# uMultimeter__Sch_View.net
KiCad netlist of a schematic drawn in Altium Designer
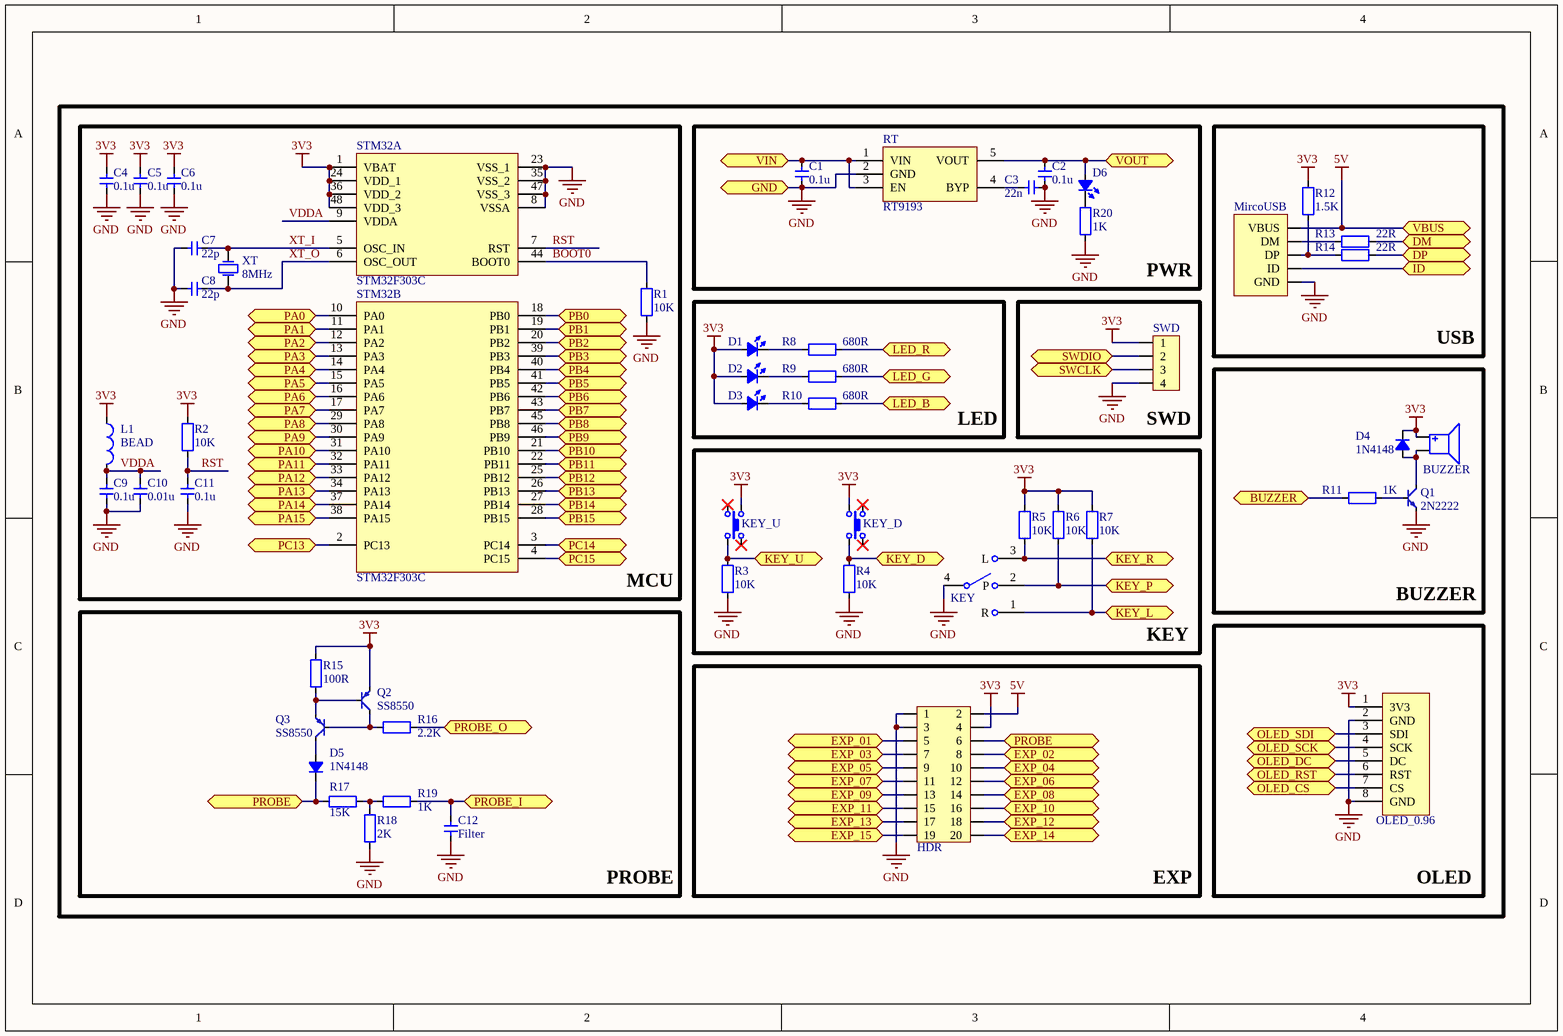
[diagram p0: uMultimeter__Sch_View.SchDoc]

(export (version "E")
  (design (tool "Eeschema 10.0.6"))
  (components
    (comp (ref "BUZZER")
      (value "Buzzer")
      (footprint "PCB_Module:Buzzer_5x5")
      (libsource (lib "SCH_Module") (part "Buzzer"))
    )
    (comp (ref "C1")
      (value "0.1u")
      (footprint "PCB_PassiveCap:CAP_0603")
      (description "Capacitor")
      (fields (field (name "Comment") "Cap_0603"))
      (libsource (lib "SCH_Passive") (part "Cap_0603"))
    )
    (comp (ref "C2")
      (value "0.1u")
      (footprint "PCB_PassiveCap:CAP_0603")
      (description "Capacitor")
      (fields (field (name "Comment") "Cap_0603"))
      (libsource (lib "SCH_Passive") (part "Cap_0603"))
    )
    (comp (ref "C3")
      (value "22n")
      (footprint "PCB_PassiveCap:CAP_0603")
      (description "Capacitor")
      (fields (field (name "Comment") "Cap_0603"))
      (libsource (lib "SCH_Passive") (part "Cap_0603"))
    )
    (comp (ref "C4")
      (value "0.1u")
      (footprint "PCB_PassiveCap:CAP_0603")
      (description "Capacitor")
      (fields (field (name "Comment") "Cap_0603"))
      (libsource (lib "SCH_Passive") (part "Cap_0603"))
    )
    (comp (ref "C5")
      (value "0.1u")
      (footprint "PCB_PassiveCap:CAP_0603")
      (description "Capacitor")
      (fields (field (name "Comment") "Cap_0603"))
      (libsource (lib "SCH_Passive") (part "Cap_0603"))
    )
    (comp (ref "C6")
      (value "0.1u")
      (footprint "PCB_PassiveCap:CAP_0603")
      (description "Capacitor")
      (fields (field (name "Comment") "Cap_0603"))
      (libsource (lib "SCH_Passive") (part "Cap_0603"))
    )
    (comp (ref "C7")
      (value "22p")
      (footprint "PCB_PassiveCap:CAP_0603")
      (description "Capacitor")
      (fields (field (name "Comment") "Cap_0603"))
      (libsource (lib "SCH_Passive") (part "Cap_0603"))
    )
    (comp (ref "C8")
      (value "22p")
      (footprint "PCB_PassiveCap:CAP_0603")
      (description "Capacitor")
      (fields (field (name "Comment") "Cap_0603"))
      (libsource (lib "SCH_Passive") (part "Cap_0603"))
    )
    (comp (ref "C9")
      (value "0.1u")
      (footprint "PCB_PassiveCap:CAP_0603")
      (description "Capacitor")
      (fields (field (name "Comment") "Cap_0603"))
      (libsource (lib "SCH_Passive") (part "Cap_0603"))
    )
    (comp (ref "C10")
      (value "0.01u")
      (footprint "PCB_PassiveCap:CAP_0603")
      (description "Capacitor")
      (fields (field (name "Comment") "Cap_0603"))
      (libsource (lib "SCH_Passive") (part "Cap_0603"))
    )
    (comp (ref "C11")
      (value "0.1u")
      (footprint "PCB_PassiveCap:CAP_0603")
      (description "Capacitor")
      (fields (field (name "Comment") "Cap_0603"))
      (libsource (lib "SCH_Passive") (part "Cap_0603"))
    )
    (comp (ref "C12")
      (value "Filter")
      (footprint "PCB_PassiveCap:CAP_0603")
      (description "Capacitor")
      (fields (field (name "Comment") "Cap_0603"))
      (libsource (lib "SCH_Passive") (part "Cap_0603"))
    )
    (comp (ref "D1")
      (value "LED_0805")
      (footprint "PCB_ActiveLED:LED_0805_RED")
      (description "LED")
      (libsource (lib "SCH_Active") (part "LED_0805"))
    )
    (comp (ref "D2")
      (value "LED_0805")
      (footprint "PCB_ActiveLED:LED_0805_GREEN")
      (description "LED")
      (libsource (lib "SCH_Active") (part "LED_0805"))
    )
    (comp (ref "D3")
      (value "LED_0805")
      (footprint "PCB_ActiveLED:LED_0805_BLUE")
      (description "LED")
      (libsource (lib "SCH_Active") (part "LED_0805"))
    )
    (comp (ref "D4")
      (value "1N4148")
      (footprint "PCB_ActiveDIO:SOD-323")
      (description "Diode")
      (fields (field (name "Comment") "Diode_SOD323"))
      (libsource (lib "SCH_Active") (part "Diode_SOD323"))
    )
    (comp (ref "D5")
      (value "1N4148")
      (footprint "PCB_ActiveDIO:SOD-323")
      (description "Diode")
      (fields (field (name "Comment") "Diode_SOD323"))
      (libsource (lib "SCH_Active") (part "Diode_SOD323"))
    )
    (comp (ref "D6")
      (value "LED_0805")
      (footprint "PCB_ActiveLED:LED_0805_ORANGE")
      (description "LED")
      (libsource (lib "SCH_Active") (part "LED_0805"))
    )
    (comp (ref "HDR")
      (value "HDR2x10_2.54")
      (footprint "PCB_ConnectorHDR:HDR2X10_2.54_180HF")
      (description "Header")
      (libsource (lib "SCH_ConnectorHDR") (part "HDR2x10_2.54"))
    )
    (comp (ref "KEY")
      (value "ButtonPushLever_11*12_90")
      (footprint "PCB_Switch:ButtonPushLever_11*12_90")
      (description "Button")
      (libsource (lib "SCH_Switch") (part "ButtonPushLever_11*12_90"))
    )
    (comp (ref "KEY_D")
      (value "ButtonTACT")
      (footprint "PCB_Switch:ButtonTACT_3.5*3.55_90")
      (description "Button")
      (libsource (lib "SCH_Switch") (part "ButtonTACT"))
    )
    (comp (ref "KEY_U")
      (value "ButtonTACT")
      (footprint "PCB_Switch:ButtonTACT_3.5*3.55_90")
      (description "Button")
      (libsource (lib "SCH_Switch") (part "ButtonTACT"))
    )
    (comp (ref "L1")
      (value "BEAD")
      (footprint "PCB_PassiveInd:IND_0603")
      (description "Inductor")
      (fields (field (name "Comment") "Ind_0603"))
      (libsource (lib "SCH_Passive") (part "Ind_0603"))
    )
    (comp (ref "MircoUSB")
      (value "USB_Micro")
      (footprint "PCB_USB:USB_Micro-AB")
      (description "USB")
      (libsource (lib "SCH_USB") (part "USB_Micro"))
    )
    (comp (ref "OLED_0.96")
      (value "OLED_0.96")
      (footprint "PCB_Module:OLED_0.96_96x64_v2")
      (description "Module")
      (libsource (lib "SCH_Module") (part "OLED_0.96_96*64_v2"))
    )
    (comp (ref "Q1")
      (value "2N2222")
      (footprint "PCB_IntegratedCircuit:SOT23-3")
      (description "Transistor")
      (fields (field (name "Comment") "BJT_NPN"))
      (libsource (lib "SCH_Active") (part "BJT_NPN"))
    )
    (comp (ref "Q2")
      (value "SS8550")
      (footprint "PCB_IntegratedCircuit:SOT23-3")
      (description "Transistor")
      (fields (field (name "Comment") "BJT_PNP"))
      (libsource (lib "SCH_Active") (part "BJT_PNP"))
    )
    (comp (ref "Q3")
      (value "SS8550")
      (footprint "PCB_IntegratedCircuit:SOT23-3")
      (description "Transistor")
      (fields (field (name "Comment") "BJT_PNP"))
      (libsource (lib "SCH_Active") (part "BJT_PNP"))
    )
    (comp (ref "R1")
      (value "10K")
      (footprint "PCB_PassiveRes:RES_0603")
      (description "Resistor")
      (fields (field (name "Comment") "Res_0603"))
      (libsource (lib "") (part "Res_0603_1"))
    )
    (comp (ref "R2")
      (value "10K")
      (footprint "PCB_PassiveRes:RES_0603")
      (description "Resistor")
      (fields (field (name "Comment") "Res_0603"))
      (libsource (lib "") (part "Res_0603_1"))
    )
    (comp (ref "R3")
      (value "10K")
      (footprint "PCB_PassiveRes:RES_0603")
      (description "Resistor")
      (fields (field (name "Comment") "Res_0603"))
      (libsource (lib "") (part "Res_0603_1"))
    )
    (comp (ref "R4")
      (value "10K")
      (footprint "PCB_PassiveRes:RES_0603")
      (description "Resistor")
      (fields (field (name "Comment") "Res_0603"))
      (libsource (lib "") (part "Res_0603_1"))
    )
    (comp (ref "R5")
      (value "10K")
      (footprint "PCB_PassiveRes:RES_0603")
      (description "Resistor")
      (fields (field (name "Comment") "Res_0603"))
      (libsource (lib "") (part "Res_0603_1"))
    )
    (comp (ref "R6")
      (value "10K")
      (footprint "PCB_PassiveRes:RES_0603")
      (description "Resistor")
      (fields (field (name "Comment") "Res_0603"))
      (libsource (lib "") (part "Res_0603_1"))
    )
    (comp (ref "R7")
      (value "10K")
      (footprint "PCB_PassiveRes:RES_0603")
      (description "Resistor")
      (fields (field (name "Comment") "Res_0603"))
      (libsource (lib "") (part "Res_0603_1"))
    )
    (comp (ref "R8")
      (value "680R")
      (footprint "PCB_PassiveRes:RES_0603")
      (description "Resistor")
      (fields (field (name "Comment") "Res_0603"))
      (libsource (lib "SCH_Passive") (part "Res_0603"))
    )
    (comp (ref "R9")
      (value "680R")
      (footprint "PCB_PassiveRes:RES_0603")
      (description "Resistor")
      (fields (field (name "Comment") "Res_0603"))
      (libsource (lib "SCH_Passive") (part "Res_0603"))
    )
    (comp (ref "R10")
      (value "680R")
      (footprint "PCB_PassiveRes:RES_0603")
      (description "Resistor")
      (fields (field (name "Comment") "Res_0603"))
      (libsource (lib "") (part "Res_0603_2"))
    )
    (comp (ref "R11")
      (value "1K")
      (footprint "PCB_PassiveRes:RES_0603")
      (description "Resistor")
      (fields (field (name "Comment") "Res_0603"))
      (libsource (lib "SCH_Passive") (part "Res_0603"))
    )
    (comp (ref "R12")
      (value "1.5K")
      (footprint "PCB_PassiveRes:RES_0603")
      (description "Resistor")
      (fields (field (name "Comment") "Res_0603"))
      (libsource (lib "") (part "Res_0603_3"))
    )
    (comp (ref "R13")
      (value "22R")
      (footprint "PCB_PassiveRes:RES_0603")
      (description "Resistor")
      (fields (field (name "Comment") "Res_0603"))
      (libsource (lib "") (part "Res_0603_2"))
    )
    (comp (ref "R14")
      (value "22R")
      (footprint "PCB_PassiveRes:RES_0603")
      (description "Resistor")
      (fields (field (name "Comment") "Res_0603"))
      (libsource (lib "") (part "Res_0603_2"))
    )
    (comp (ref "R15")
      (value "100R")
      (footprint "PCB_PassiveRes:RES_0603")
      (description "Resistor")
      (fields (field (name "Comment") "Res_0603"))
      (libsource (lib "") (part "Res_0603_1"))
    )
    (comp (ref "R16")
      (value "2.2K")
      (footprint "PCB_PassiveRes:RES_0603")
      (description "Resistor")
      (fields (field (name "Comment") "Res_0603"))
      (libsource (lib "SCH_Passive") (part "Res_0603"))
    )
    (comp (ref "R17")
      (value "15K")
      (footprint "PCB_PassiveRes:RES_0603")
      (description "Resistor")
      (fields (field (name "Comment") "Res_0603"))
      (libsource (lib "SCH_Passive") (part "Res_0603"))
    )
    (comp (ref "R18")
      (value "2K")
      (footprint "PCB_PassiveRes:RES_0603")
      (description "Resistor")
      (fields (field (name "Comment") "Res_0603"))
      (libsource (lib "") (part "Res_0603_3"))
    )
    (comp (ref "R19")
      (value "1K")
      (footprint "PCB_PassiveRes:RES_0603")
      (description "Resistor")
      (fields (field (name "Comment") "Res_0603"))
      (libsource (lib "") (part "Res_0603_2"))
    )
    (comp (ref "R20")
      (value "1K")
      (footprint "PCB_PassiveRes:RES_0603")
      (description "Resistor")
      (fields (field (name "Comment") "Res_0603"))
      (libsource (lib "") (part "Res_0603_3"))
    )
    (comp (ref "RT")
      (value "RT9193")
      (footprint "PCB_IntegratedCircuit:SOT23-5")
      (description "Power")
      (libsource (lib "SCH_IntegratedCircuit") (part "SP6205"))
    )
    (comp (ref "STM32")
      (value "STM32F303C")
      (footprint "PCB_IntegratedCircuit:LQFP_P0.5_48")
      (description "MCU")
      (libsource (lib "SCH_IntegratedCircuit") (part "STM32F303C"))
    )
    (comp (ref "SWD")
      (value "HDR1x4_1.27")
      (footprint "PCB_ConnectorHDR:HDR1X4_1.27_180")
      (description "Header")
      (libsource (lib "SCH_ConnectorHDR") (part "HDR1x4_1.27"))
    )
    (comp (ref "XT")
      (value "8MHz")
      (footprint "PCB_Oscillator:XT_5032_2")
      (description "Crystal Oscillator")
      (fields (field (name "Comment") "XTAL_5032_2P"))
      (libsource (lib "SCH_Oscillator") (part "XTAL_5032_2P"))
    )
  )
  (nets
    (net (code "1") (name "/BOOT0") (class "Default")
      (node (ref "R1") (pin "2") (pinfunction "2_2") (pintype "passive"))
      (node (ref "STM32") (pin "44") (pinfunction "BOOT0_44") (pintype "passive"))
    )
    (net (code "2") (name "/BUZZER") (class "Default")
      (node (ref "R11") (pin "2") (pinfunction "2_2") (pintype "passive"))
    )
    (net (code "3") (name "/DM") (class "Default")
      (node (ref "R13") (pin "2") (pinfunction "2_2") (pintype "passive"))
    )
    (net (code "4") (name "/DP") (class "Default")
      (node (ref "R14") (pin "2") (pinfunction "2_2") (pintype "passive"))
    )
    (net (code "5") (name "/EXP_01") (class "Default")
      (node (ref "HDR") (pin "5") (pinfunction "5_5") (pintype "passive"))
    )
    (net (code "6") (name "/EXP_02") (class "Default")
      (node (ref "HDR") (pin "8") (pinfunction "8_8") (pintype "passive"))
    )
    (net (code "7") (name "/EXP_03") (class "Default")
      (node (ref "HDR") (pin "7") (pinfunction "7_7") (pintype "passive"))
    )
    (net (code "8") (name "/EXP_04") (class "Default")
      (node (ref "HDR") (pin "10") (pinfunction "10_10") (pintype "passive"))
    )
    (net (code "9") (name "/EXP_05") (class "Default")
      (node (ref "HDR") (pin "9") (pinfunction "9_9") (pintype "passive"))
    )
    (net (code "10") (name "/EXP_06") (class "Default")
      (node (ref "HDR") (pin "12") (pinfunction "12_12") (pintype "passive"))
    )
    (net (code "11") (name "/EXP_07") (class "Default")
      (node (ref "HDR") (pin "11") (pinfunction "11_11") (pintype "passive"))
    )
    (net (code "12") (name "/EXP_08") (class "Default")
      (node (ref "HDR") (pin "14") (pinfunction "14_14") (pintype "passive"))
    )
    (net (code "13") (name "/EXP_09") (class "Default")
      (node (ref "HDR") (pin "13") (pinfunction "13_13") (pintype "passive"))
    )
    (net (code "14") (name "/EXP_10") (class "Default")
      (node (ref "HDR") (pin "16") (pinfunction "16_16") (pintype "passive"))
    )
    (net (code "15") (name "/EXP_11") (class "Default")
      (node (ref "HDR") (pin "15") (pinfunction "15_15") (pintype "passive"))
    )
    (net (code "16") (name "/EXP_12") (class "Default")
      (node (ref "HDR") (pin "18") (pinfunction "18_18") (pintype "passive"))
    )
    (net (code "17") (name "/EXP_13") (class "Default")
      (node (ref "HDR") (pin "17") (pinfunction "17_17") (pintype "passive"))
    )
    (net (code "18") (name "/EXP_14") (class "Default")
      (node (ref "HDR") (pin "20") (pinfunction "20_20") (pintype "passive"))
    )
    (net (code "19") (name "/EXP_15") (class "Default")
      (node (ref "HDR") (pin "19") (pinfunction "19_19") (pintype "passive"))
    )
    (net (code "20") (name "/ID") (class "Default")
      (node (ref "MircoUSB") (pin "4") (pinfunction "ID_4") (pintype "passive"))
    )
    (net (code "21") (name "/KEY_D") (class "Default")
      (node (ref "KEY_D") (pin "4") (pinfunction "4_4") (pintype "passive"))
      (node (ref "R4") (pin "2") (pinfunction "2_2") (pintype "passive"))
    )
    (net (code "22") (name "/KEY_L") (class "Default")
      (node (ref "KEY") (pin "1") (pinfunction "R_1") (pintype "passive"))
      (node (ref "R7") (pin "1") (pinfunction "1_1") (pintype "passive"))
    )
    (net (code "23") (name "/KEY_P") (class "Default")
      (node (ref "KEY") (pin "2") (pinfunction "P_2") (pintype "passive"))
      (node (ref "R6") (pin "1") (pinfunction "1_1") (pintype "passive"))
    )
    (net (code "24") (name "/KEY_R") (class "Default")
      (node (ref "KEY") (pin "3") (pinfunction "L_3") (pintype "passive"))
      (node (ref "R5") (pin "1") (pinfunction "1_1") (pintype "passive"))
    )
    (net (code "25") (name "/KEY_U") (class "Default")
      (node (ref "KEY_U") (pin "4") (pinfunction "4_4") (pintype "passive"))
      (node (ref "R3") (pin "2") (pinfunction "2_2") (pintype "passive"))
    )
    (net (code "26") (name "/LED_B") (class "Default")
      (node (ref "R10") (pin "2") (pinfunction "2_2") (pintype "passive"))
    )
    (net (code "27") (name "/LED_G") (class "Default")
      (node (ref "R9") (pin "1") (pinfunction "1_1") (pintype "passive"))
    )
    (net (code "28") (name "/LED_R") (class "Default")
      (node (ref "R8") (pin "1") (pinfunction "1_1") (pintype "passive"))
    )
    (net (code "29") (name "/OLED_CS") (class "Default")
      (node (ref "OLED_0.96") (pin "7") (pinfunction "CS_7") (pintype "passive"))
    )
    (net (code "30") (name "/OLED_DC") (class "Default")
      (node (ref "OLED_0.96") (pin "5") (pinfunction "DC_5") (pintype "passive"))
    )
    (net (code "31") (name "/OLED_RST") (class "Default")
      (node (ref "OLED_0.96") (pin "6") (pinfunction "RST_6") (pintype "passive"))
    )
    (net (code "32") (name "/OLED_SCK") (class "Default")
      (node (ref "OLED_0.96") (pin "4") (pinfunction "SCK_4") (pintype "passive"))
    )
    (net (code "33") (name "/OLED_SDI") (class "Default")
      (node (ref "OLED_0.96") (pin "3") (pinfunction "SDI_3") (pintype "passive"))
    )
    (net (code "34") (name "/PA0") (class "Default")
      (node (ref "STM32") (pin "10") (pinfunction "PA0_10") (pintype "passive"))
    )
    (net (code "35") (name "/PA1") (class "Default")
      (node (ref "STM32") (pin "11") (pinfunction "PA1_11") (pintype "passive"))
    )
    (net (code "36") (name "/PA2") (class "Default")
      (node (ref "STM32") (pin "12") (pinfunction "PA2_12") (pintype "passive"))
    )
    (net (code "37") (name "/PA3") (class "Default")
      (node (ref "STM32") (pin "13") (pinfunction "PA3_13") (pintype "passive"))
    )
    (net (code "38") (name "/PA4") (class "Default")
      (node (ref "STM32") (pin "14") (pinfunction "PA4_14") (pintype "passive"))
    )
    (net (code "39") (name "/PA5") (class "Default")
      (node (ref "STM32") (pin "15") (pinfunction "PA5_15") (pintype "passive"))
    )
    (net (code "40") (name "/PA6") (class "Default")
      (node (ref "STM32") (pin "16") (pinfunction "PA6_16") (pintype "passive"))
    )
    (net (code "41") (name "/PA7") (class "Default")
      (node (ref "STM32") (pin "17") (pinfunction "PA7_17") (pintype "passive"))
    )
    (net (code "42") (name "/PA8") (class "Default")
      (node (ref "STM32") (pin "29") (pinfunction "PA8_29") (pintype "passive"))
    )
    (net (code "43") (name "/PA9") (class "Default")
      (node (ref "STM32") (pin "30") (pinfunction "PA9_30") (pintype "passive"))
    )
    (net (code "44") (name "/PA10") (class "Default")
      (node (ref "STM32") (pin "31") (pinfunction "PA10_31") (pintype "passive"))
    )
    (net (code "45") (name "/PA11") (class "Default")
      (node (ref "STM32") (pin "32") (pinfunction "PA11_32") (pintype "passive"))
    )
    (net (code "46") (name "/PA12") (class "Default")
      (node (ref "STM32") (pin "33") (pinfunction "PA12_33") (pintype "passive"))
    )
    (net (code "47") (name "/PA13") (class "Default")
      (node (ref "STM32") (pin "34") (pinfunction "PA13_34") (pintype "passive"))
    )
    (net (code "48") (name "/PA14") (class "Default")
      (node (ref "STM32") (pin "37") (pinfunction "PA14_37") (pintype "passive"))
    )
    (net (code "49") (name "/PA15") (class "Default")
      (node (ref "STM32") (pin "38") (pinfunction "PA15_38") (pintype "passive"))
    )
    (net (code "50") (name "/PB0") (class "Default")
      (node (ref "STM32") (pin "18") (pinfunction "PB0_18") (pintype "passive"))
    )
    (net (code "51") (name "/PB1") (class "Default")
      (node (ref "STM32") (pin "19") (pinfunction "PB1_19") (pintype "passive"))
    )
    (net (code "52") (name "/PB2") (class "Default")
      (node (ref "STM32") (pin "20") (pinfunction "PB2_20") (pintype "passive"))
    )
    (net (code "53") (name "/PB3") (class "Default")
      (node (ref "STM32") (pin "39") (pinfunction "PB3_39") (pintype "passive"))
    )
    (net (code "54") (name "/PB4") (class "Default")
      (node (ref "STM32") (pin "40") (pinfunction "PB4_40") (pintype "passive"))
    )
    (net (code "55") (name "/PB5") (class "Default")
      (node (ref "STM32") (pin "41") (pinfunction "PB5_41") (pintype "passive"))
    )
    (net (code "56") (name "/PB6") (class "Default")
      (node (ref "STM32") (pin "42") (pinfunction "PB6_42") (pintype "passive"))
    )
    (net (code "57") (name "/PB7") (class "Default")
      (node (ref "STM32") (pin "43") (pinfunction "PB7_43") (pintype "passive"))
    )
    (net (code "58") (name "/PB8") (class "Default")
      (node (ref "STM32") (pin "45") (pinfunction "PB8_45") (pintype "passive"))
    )
    (net (code "59") (name "/PB9") (class "Default")
      (node (ref "STM32") (pin "46") (pinfunction "PB9_46") (pintype "passive"))
    )
    (net (code "60") (name "/PB10") (class "Default")
      (node (ref "STM32") (pin "21") (pinfunction "PB10_21") (pintype "passive"))
    )
    (net (code "61") (name "/PB11") (class "Default")
      (node (ref "STM32") (pin "22") (pinfunction "PB11_22") (pintype "passive"))
    )
    (net (code "62") (name "/PB12") (class "Default")
      (node (ref "STM32") (pin "25") (pinfunction "PB12_25") (pintype "passive"))
    )
    (net (code "63") (name "/PB13") (class "Default")
      (node (ref "STM32") (pin "26") (pinfunction "PB13_26") (pintype "passive"))
    )
    (net (code "64") (name "/PB14") (class "Default")
      (node (ref "STM32") (pin "27") (pinfunction "PB14_27") (pintype "passive"))
    )
    (net (code "65") (name "/PB15") (class "Default")
      (node (ref "STM32") (pin "28") (pinfunction "PB15_28") (pintype "passive"))
    )
    (net (code "66") (name "/PC13") (class "Default")
      (node (ref "STM32") (pin "2") (pinfunction "PC13_2") (pintype "passive"))
    )
    (net (code "67") (name "/PC14") (class "Default")
      (node (ref "STM32") (pin "3") (pinfunction "PC14_3") (pintype "passive"))
    )
    (net (code "68") (name "/PC15") (class "Default")
      (node (ref "STM32") (pin "4") (pinfunction "PC15_4") (pintype "passive"))
    )
    (net (code "69") (name "/PROBE") (class "Default")
      (node (ref "D5") (pin "2") (pinfunction "K_2") (pintype "passive"))
      (node (ref "HDR") (pin "6") (pinfunction "6_6") (pintype "passive"))
      (node (ref "R17") (pin "2") (pinfunction "2_2") (pintype "passive"))
    )
    (net (code "70") (name "/PROBE_I") (class "Default")
      (node (ref "C12") (pin "2") (pinfunction "2_2") (pintype "passive"))
      (node (ref "R19") (pin "2") (pinfunction "2_2") (pintype "passive"))
    )
    (net (code "71") (name "/PROBE_O") (class "Default")
      (node (ref "R16") (pin "1") (pinfunction "1_1") (pintype "passive"))
    )
    (net (code "72") (name "/RST") (class "Default")
      (node (ref "C11") (pin "2") (pinfunction "2_2") (pintype "passive"))
      (node (ref "R2") (pin "1") (pinfunction "1_1") (pintype "passive"))
      (node (ref "STM32") (pin "7") (pinfunction "RST_7") (pintype "passive"))
    )
    (net (code "73") (name "/SWCLK") (class "Default")
      (node (ref "SWD") (pin "3") (pinfunction "3_3") (pintype "passive"))
    )
    (net (code "74") (name "/SWDIO") (class "Default")
      (node (ref "SWD") (pin "2") (pinfunction "2_2") (pintype "passive"))
    )
    (net (code "75") (name "/VDDA") (class "Default")
      (node (ref "C10") (pin "2") (pinfunction "2_2") (pintype "passive"))
      (node (ref "C9") (pin "2") (pinfunction "2_2") (pintype "passive"))
      (node (ref "L1") (pin "2") (pinfunction "2_2") (pintype "passive"))
      (node (ref "STM32") (pin "9") (pinfunction "VDDA_9") (pintype "passive"))
    )
    (net (code "76") (name "/VIN") (class "Default")
      (node (ref "C1") (pin "2") (pinfunction "2_2") (pintype "passive"))
      (node (ref "RT") (pin "1") (pinfunction "VIN_1") (pintype "passive"))
      (node (ref "RT") (pin "3") (pinfunction "EN_3") (pintype "power_in"))
    )
    (net (code "77") (name "/VOUT") (class "Default")
      (node (ref "C2") (pin "2") (pinfunction "2_2") (pintype "passive"))
      (node (ref "D6") (pin "1") (pinfunction "A_1") (pintype "passive"))
      (node (ref "RT") (pin "5") (pinfunction "VOUT_5") (pintype "passive"))
    )
    (net (code "78") (name "/XT_I") (class "Default")
      (node (ref "C7") (pin "1") (pinfunction "1_1") (pintype "passive"))
      (node (ref "STM32") (pin "5") (pinfunction "OSC_IN_5") (pintype "passive"))
      (node (ref "XT") (pin "2") (pinfunction "OSC2_2") (pintype "passive"))
    )
    (net (code "79") (name "/XT_O") (class "Default")
      (node (ref "C8") (pin "1") (pinfunction "1_1") (pintype "passive"))
      (node (ref "STM32") (pin "6") (pinfunction "OSC_OUT_6") (pintype "passive"))
      (node (ref "XT") (pin "1") (pinfunction "OSC1_1") (pintype "passive"))
    )
    (net (code "80") (name "3V3") (class "Default")
      (node (ref "BUZZER") (pin "P") (pinfunction "Positive_P") (pintype "passive"))
      (node (ref "C4") (pin "2") (pinfunction "2_2") (pintype "passive"))
      (node (ref "C5") (pin "2") (pinfunction "2_2") (pintype "passive"))
      (node (ref "C6") (pin "2") (pinfunction "2_2") (pintype "passive"))
      (node (ref "D1") (pin "1") (pinfunction "A_1") (pintype "passive"))
      (node (ref "D2") (pin "1") (pinfunction "A_1") (pintype "passive"))
      (node (ref "D3") (pin "1") (pinfunction "A_1") (pintype "passive"))
      (node (ref "D4") (pin "2") (pinfunction "K_2") (pintype "passive"))
      (node (ref "HDR") (pin "4") (pinfunction "4_4") (pintype "passive"))
      (node (ref "KEY_D") (pin "3") (pinfunction "3_3") (pintype "passive"))
      (node (ref "KEY_U") (pin "1") (pinfunction "1_1") (pintype "passive"))
      (node (ref "L1") (pin "1") (pinfunction "1_1") (pintype "passive"))
      (node (ref "OLED_0.96") (pin "1") (pinfunction "3V3_1") (pintype "passive"))
      (node (ref "Q2") (pin "2") (pinfunction "E_2") (pintype "passive"))
      (node (ref "R12") (pin "1") (pinfunction "1_1") (pintype "passive"))
      (node (ref "R15") (pin "2") (pinfunction "2_2") (pintype "passive"))
      (node (ref "R2") (pin "2") (pinfunction "2_2") (pintype "passive"))
      (node (ref "R5") (pin "2") (pinfunction "2_2") (pintype "passive"))
      (node (ref "R6") (pin "2") (pinfunction "2_2") (pintype "passive"))
      (node (ref "R7") (pin "2") (pinfunction "2_2") (pintype "passive"))
      (node (ref "STM32") (pin "1") (pinfunction "VBAT_1") (pintype "passive"))
      (node (ref "STM32") (pin "24") (pinfunction "VDD_1_24") (pintype "passive"))
      (node (ref "STM32") (pin "36") (pinfunction "VDD_2_36") (pintype "passive"))
      (node (ref "STM32") (pin "48") (pinfunction "VDD_3_48") (pintype "passive"))
      (node (ref "SWD") (pin "1") (pinfunction "1_1") (pintype "passive"))
    )
    (net (code "81") (name "5V") (class "Default")
      (node (ref "HDR") (pin "2") (pinfunction "2_2") (pintype "passive"))
      (node (ref "MircoUSB") (pin "1") (pinfunction "VBUS_1") (pintype "passive"))
    )
    (net (code "82") (name "GND") (class "Default")
      (node (ref "C1") (pin "1") (pinfunction "1_1") (pintype "passive"))
      (node (ref "C10") (pin "1") (pinfunction "1_1") (pintype "passive"))
      (node (ref "C11") (pin "1") (pinfunction "1_1") (pintype "passive"))
      (node (ref "C12") (pin "1") (pinfunction "1_1") (pintype "passive"))
      (node (ref "C2") (pin "1") (pinfunction "1_1") (pintype "passive"))
      (node (ref "C3") (pin "1") (pinfunction "1_1") (pintype "passive"))
      (node (ref "C4") (pin "1") (pinfunction "1_1") (pintype "passive"))
      (node (ref "C5") (pin "1") (pinfunction "1_1") (pintype "passive"))
      (node (ref "C6") (pin "1") (pinfunction "1_1") (pintype "passive"))
      (node (ref "C7") (pin "2") (pinfunction "2_2") (pintype "passive"))
      (node (ref "C8") (pin "2") (pinfunction "2_2") (pintype "passive"))
      (node (ref "C9") (pin "1") (pinfunction "1_1") (pintype "passive"))
      (node (ref "HDR") (pin "1") (pinfunction "1_1") (pintype "passive"))
      (node (ref "HDR") (pin "3") (pinfunction "3_3") (pintype "passive"))
      (node (ref "KEY") (pin "4") (pinfunction "4_4") (pintype "passive"))
      (node (ref "MircoUSB") (pin "5") (pinfunction "GND_5") (pintype "passive"))
      (node (ref "OLED_0.96") (pin "2") (pinfunction "GND_2") (pintype "passive"))
      (node (ref "OLED_0.96") (pin "8") (pinfunction "GND_8") (pintype "passive"))
      (node (ref "Q1") (pin "2") (pinfunction "E_2") (pintype "passive"))
      (node (ref "R1") (pin "1") (pinfunction "1_1") (pintype "passive"))
      (node (ref "R18") (pin "2") (pinfunction "2_2") (pintype "passive"))
      (node (ref "R20") (pin "2") (pinfunction "2_2") (pintype "passive"))
      (node (ref "R3") (pin "1") (pinfunction "1_1") (pintype "passive"))
      (node (ref "R4") (pin "1") (pinfunction "1_1") (pintype "passive"))
      (node (ref "RT") (pin "2") (pinfunction "GND_2") (pintype "passive"))
      (node (ref "STM32") (pin "23") (pinfunction "VSS_1_23") (pintype "passive"))
      (node (ref "STM32") (pin "35") (pinfunction "VSS_2_35") (pintype "passive"))
      (node (ref "STM32") (pin "47") (pinfunction "VSS_3_47") (pintype "passive"))
      (node (ref "STM32") (pin "8") (pinfunction "VSSA_8") (pintype "passive"))
      (node (ref "SWD") (pin "4") (pinfunction "4_4") (pintype "passive"))
    )
    (net (code "83") (name "Net-(BUZZER-Negative)") (class "Default")
      (node (ref "BUZZER") (pin "N") (pinfunction "Negative_N") (pintype "passive"))
      (node (ref "D4") (pin "1") (pinfunction "A_1") (pintype "passive"))
      (node (ref "Q1") (pin "3") (pinfunction "C_3") (pintype "passive"))
    )
    (net (code "84") (name "Net-(D1-K)") (class "Default")
      (node (ref "D1") (pin "2") (pinfunction "K_2") (pintype "passive"))
      (node (ref "R8") (pin "2") (pinfunction "2_2") (pintype "passive"))
    )
    (net (code "85") (name "Net-(D2-K)") (class "Default")
      (node (ref "D2") (pin "2") (pinfunction "K_2") (pintype "passive"))
      (node (ref "R9") (pin "2") (pinfunction "2_2") (pintype "passive"))
    )
    (net (code "86") (name "Net-(D3-K)") (class "Default")
      (node (ref "D3") (pin "2") (pinfunction "K_2") (pintype "passive"))
      (node (ref "R10") (pin "1") (pinfunction "1_1") (pintype "passive"))
    )
    (net (code "87") (name "Net-(D5-A)") (class "Default")
      (node (ref "D5") (pin "1") (pinfunction "A_1") (pintype "passive"))
      (node (ref "Q3") (pin "3") (pinfunction "C_3") (pintype "passive"))
    )
    (net (code "88") (name "Net-(D6-K)") (class "Default")
      (node (ref "D6") (pin "2") (pinfunction "K_2") (pintype "passive"))
      (node (ref "R20") (pin "1") (pinfunction "1_1") (pintype "passive"))
    )
    (net (code "89") (name "Net-(MircoUSB-DM)") (class "Default")
      (node (ref "MircoUSB") (pin "2") (pinfunction "DM_2") (pintype "passive"))
      (node (ref "R13") (pin "1") (pinfunction "1_1") (pintype "passive"))
    )
    (net (code "90") (name "Net-(MircoUSB-DP)") (class "Default")
      (node (ref "MircoUSB") (pin "3") (pinfunction "DP_3") (pintype "passive"))
      (node (ref "R12") (pin "2") (pinfunction "2_2") (pintype "passive"))
      (node (ref "R14") (pin "1") (pinfunction "1_1") (pintype "passive"))
    )
    (net (code "91") (name "Net-(Q1-B)") (class "Default")
      (node (ref "Q1") (pin "1") (pinfunction "B_1") (pintype "passive"))
      (node (ref "R11") (pin "1") (pinfunction "1_1") (pintype "passive"))
    )
    (net (code "92") (name "Net-(Q2-B)") (class "Default")
      (node (ref "Q2") (pin "1") (pinfunction "B_1") (pintype "passive"))
      (node (ref "Q3") (pin "2") (pinfunction "E_2") (pintype "passive"))
      (node (ref "R15") (pin "1") (pinfunction "1_1") (pintype "passive"))
    )
    (net (code "93") (name "Net-(Q2-C)") (class "Default")
      (node (ref "Q2") (pin "3") (pinfunction "C_3") (pintype "passive"))
      (node (ref "Q3") (pin "1") (pinfunction "B_1") (pintype "passive"))
      (node (ref "R16") (pin "2") (pinfunction "2_2") (pintype "passive"))
    )
    (net (code "94") (name "Net-(R17-Pad1)") (class "Default")
      (node (ref "R17") (pin "1") (pinfunction "1_1") (pintype "passive"))
      (node (ref "R18") (pin "1") (pinfunction "1_1") (pintype "passive"))
      (node (ref "R19") (pin "1") (pinfunction "1_1") (pintype "passive"))
    )
    (net (code "95") (name "Net-(RT-BYP)") (class "Default")
      (node (ref "C3") (pin "2") (pinfunction "2_2") (pintype "passive"))
      (node (ref "RT") (pin "4") (pinfunction "BYP_4") (pintype "passive"))
    )
    (net (code "96") (name "unconnected-(KEY_D-Pad1)") (class "Default")
      (node (ref "KEY_D") (pin "1") (pinfunction "1_1") (pintype "passive+no_connect"))
    )
    (net (code "97") (name "unconnected-(KEY_D-Pad2)") (class "Default")
      (node (ref "KEY_D") (pin "2") (pinfunction "2_2") (pintype "passive+no_connect"))
    )
    (net (code "98") (name "unconnected-(KEY_U-Pad2)") (class "Default")
      (node (ref "KEY_U") (pin "2") (pinfunction "2_2") (pintype "passive+no_connect"))
    )
    (net (code "99") (name "unconnected-(KEY_U-Pad3)") (class "Default")
      (node (ref "KEY_U") (pin "3") (pinfunction "3_3") (pintype "passive+no_connect"))
    )
  )
)
